# Schematic1.net
KiCad netlist of a schematic drawn in Altium Designer
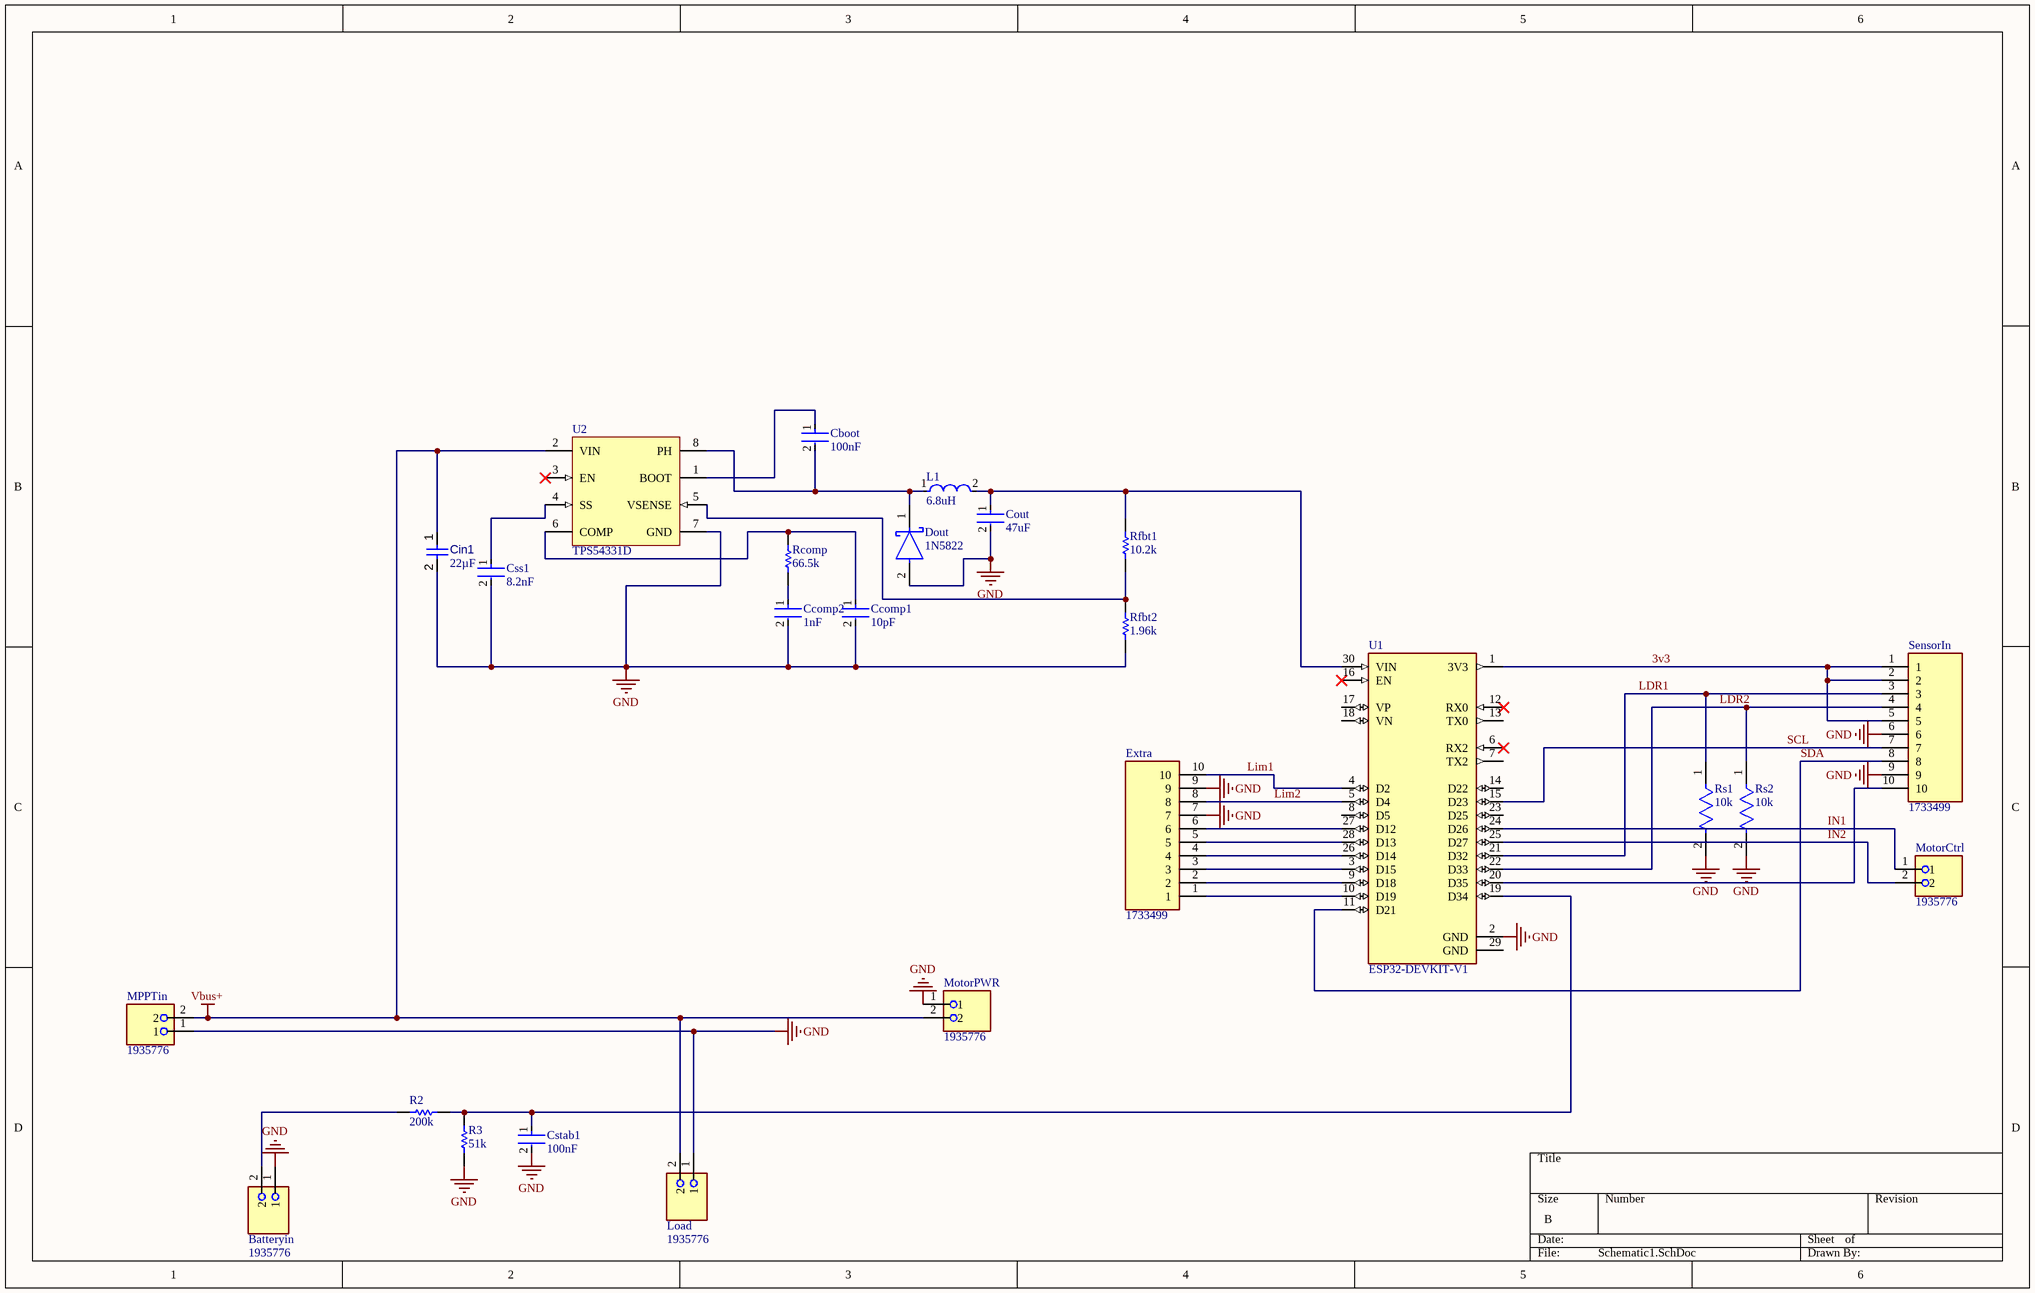
[diagram p0: Schematic1.SchDoc]

(export (version "E")
  (design (tool "Eeschema 10.0.6"))
  (components
    (comp (ref "Batteryin")
      (value "1935776")
      (footprint "PHOENIX_1935776")
      (fields (field (name "MF") "{'manufacturer': u'Phoenix Contact'}"))
      (libsource (lib "") (part "1935776_2"))
    )
    (comp (ref "Cboot")
      (value "100nF")
      (footprint "FP-CC0805-0_85-MFG")
      (description "CAP CER 0.1UF 50V X7R 0805")
      (fields (field (name "TOLERANCE") "0.1") (field (name "MANUFACTURER PART NUMBER") "CC0805KRX7R9BB104"))
      (libsource (lib "Altium Content Vault") (part "11868f565c42a9108669ba33697ecf6"))
    )
    (comp (ref "Ccomp1")
      (value "10pF")
      (footprint "FP-C0805C-DN-MFG")
      (description "Capacitor; Ceramic; Cap 10 pF; Tol 5%; Vol-Rtg 50 VDC; SMT; 0805; COG (NPO); Tape&Reel")
      (fields
        (field (name "OCTOPART") "https://octopart.com/c0805c100j5gactu-kemet-104357")
        (field (name "MANUFACTURER PART NUMBER") "C0805C100J5GACTU")
      )
      (libsource (lib "Altium Content Vault") (part "b4654b650e69147ec39a6b967a45e02"))
    )
    (comp (ref "Ccomp2")
      (value "1nF")
      (footprint "FP-CC0805-0_85-MFG")
      (description "CAP CER 0.1UF 50V X7R 0805")
      (fields (field (name "TOLERANCE") "0.1") (field (name "MANUFACTURER PART NUMBER") "CC0805KRX7R9BB104"))
      (libsource (lib "Altium Content Vault") (part "11868f565c42a9108669ba33697ecf6"))
    )
    (comp (ref "Cin1")
      (value "22µF")
      (footprint "CAPC0805(2012)145_L")
      (description "Chip Capacitor, 22µF +/-40%, 16V, 0805, Thickness 1.45 mm")
      (fields (field (name "TOLERANCE") "5%") (field (name "Comment") "Capacitor 22µF +/-40% 16V 0805"))
      (libsource (lib "Josh Mulvena") (part "CAP-NP-2"))
    )
    (comp (ref "Cout")
      (value "47uF")
      (footprint "FP-GRM21B-0_2-e0_2_0_7-IPC_A")
      (description "Chip Multilayer Ceramic Capacitors for General Purpose, 0805, 47uF, X5R, 15%, 20%, 10V")
      (fields (field (name "TOLERANCE") "20%") (field (name "VOLTAGE") "10V"))
      (libsource (lib "Altium Content Vault") (part "b4654b650e69147ec39a6b967a45e02"))
    )
    (comp (ref "Css1")
      (value "8.2nF")
      (footprint "FP-GRM219-0_1-IPC_C")
      (description "Chip Multilayer Ceramic Capacitors for General Purpose, 0805, 8200pF, C0G, 30ppm/°C, 5%, 50V")
      (fields (field (name "TOLERANCE") "5%") (field (name "VOLTAGE") "50V"))
      (libsource (lib "Altium Content Vault") (part "02cd4be3c70576c341d710602a673aa"))
    )
    (comp (ref "Cstab1")
      (value "100nF")
      (footprint "FP-CC0805-0_85-MFG")
      (description "CAP CER 0.1UF 50V X7R 0805")
      (fields (field (name "TOLERANCE") "0.1") (field (name "MANUFACTURER PART NUMBER") "CC0805KRX7R9BB104"))
      (libsource (lib "Altium Content Vault") (part "11868f565c42a9108669ba33697ecf6"))
    )
    (comp (ref "Dout")
      (value "1N5822")
      (footprint "FP-DO-201AD-MFG")
      (description "DIODE SCHOTTKY 40V 3A DO201AD")
      (fields
        (field (name "OCTOPART") "https://octopart.com/1n5822-stmicroelectronics-323225")
        (field (name "MANUFACTURER") "STMicroelectronics")
      )
      (libsource (lib "Altium Content Vault") (part "1d6ec82d83fb6aee721767c19dac4b9"))
    )
    (comp (ref "Extra")
      (value "1733499")
      (footprint "SamacSys:1733499")
      (description "Connector")
      (fields (field (name "MOUSER PART NUMBER") "651-1733499"))
      (libsource (lib "") (part "1733499_1"))
    )
    (comp (ref "L1")
      (value "6.8uH")
      (footprint "FP-MLZ2012-0_85-IPC_A")
      (description "Shielded Multilayer Inductor 6.8uH ±20% 550mA 325mΩ SMD 0805")
      (fields (field (name "TOLERANCE") "20%"))
      (libsource (lib "Altium Content Vault") (part "725321dda6339637d4d059423bc1c3c"))
    )
    (comp (ref "Load")
      (value "1935776")
      (footprint "PHOENIX_1935776")
      (fields (field (name "MF") "{'manufacturer': u'Phoenix Contact'}"))
      (libsource (lib "") (part "1935776_2"))
    )
    (comp (ref "MotorCtrl")
      (value "1935776")
      (footprint "PHOENIX_1935776")
      (fields (field (name "MF") "{'manufacturer': u'Phoenix Contact'}"))
      (libsource (lib "") (part "1935776_1"))
    )
    (comp (ref "MotorPWR")
      (value "1935776")
      (footprint "PHOENIX_1935776")
      (fields (field (name "MF") "{'manufacturer': u'Phoenix Contact'}"))
      (libsource (lib "") (part "1935776_1"))
    )
    (comp (ref "MPPTin")
      (value "1935776")
      (footprint "PHOENIX_1935776")
      (fields (field (name "MF") "{'manufacturer': u'Phoenix Contact'}"))
      (libsource (lib "1935776") (part "1935776"))
    )
    (comp (ref "R2")
      (value "200k")
      (footprint "RESC2013X50X30NL20T20")
      (fields (field (name "PART NUMBER") "CRCW0805200KJNEA") (field (name "MANUFACTURER") "Vishay Dale"))
      (libsource (lib "Altium Content Vault") (part "RES"))
    )
    (comp (ref "R3")
      (value "51k")
      (footprint "RESC2013X50X30NL20T20")
      (fields (field (name "MANUFACTURER") "Vishay Dale") (field (name "PART NUMBER") "CRCW080551K0FKEA"))
      (libsource (lib "Altium Content Vault") (part "RES"))
    )
    (comp (ref "Rcomp")
      (value "66.5k")
      (footprint "RESC2013X50X30LL20T20")
      (fields (field (name "PART NUMBER") "CRCW080566K5FKEA") (field (name "MANUFACTURER") "Vishay Dale"))
      (libsource (lib "Altium Content Vault") (part "RES"))
    )
    (comp (ref "Rfbt1")
      (value "10.2k")
      (footprint "RESC2013X50X30NL20T20")
      (fields (field (name "MANUFACTURER") "Vishay Dale") (field (name "PART NUMBER") "CRCW080510K2FKEA"))
      (libsource (lib "Altium Content Vault") (part "RES"))
    )
    (comp (ref "Rfbt2")
      (value "1.96k")
      (footprint "RESC2013X50X30LL20T20")
      (fields (field (name "PART NUMBER") "CRCW08051K96FKEA") (field (name "MANUFACTURER") "Vishay Dale"))
      (libsource (lib "Altium Content Vault") (part "RES"))
    )
    (comp (ref "Rs1")
      (value "10k")
      (footprint "FP-CRCW0805-e3-IPC_A")
      (description "RES Thick Film, 10kΩ, 1%, 0.125W, 100ppm/°C, 0805")
      (fields (field (name "TOLERANCE") "1%"))
      (libsource (lib "Altium Content Vault") (part "1029c3af85768c4190bb7ad29bc67b5"))
    )
    (comp (ref "Rs2")
      (value "10k")
      (footprint "FP-CRCW0805-e3-IPC_A")
      (description "RES Thick Film, 10kΩ, 1%, 0.125W, 100ppm/°C, 0805")
      (fields (field (name "TOLERANCE") "1%"))
      (libsource (lib "Altium Content Vault") (part "1029c3af85768c4190bb7ad29bc67b5"))
    )
    (comp (ref "SensorIn")
      (value "1733499")
      (footprint "SamacSys:1733499")
      (description "Connector")
      (fields (field (name "MOUSER PART NUMBER") "651-1733499"))
      (libsource (lib "*") (part "1733499"))
    )
    (comp (ref "U1")
      (value "ESP32-DEVKIT-V1")
      (footprint "MODULE_ESP32_DEVKIT_V1")
      (fields (field (name "MF") "Do it"))
      (libsource (lib "Josh Mulvena") (part "ESP32-DEVKIT-V1"))
    )
    (comp (ref "U2")
      (value "TPS54331D")
      (footprint "D0008A_L")
      (fields (field (name "MANUFACTURER") "Texas Instruments"))
      (libsource (lib "Altium Content Vault") (part "TI-TPS54331D8"))
    )
  )
  (nets
    (net (code "1") (name "/3v3") (class "Default")
      (node (ref "SensorIn") (pin "1") (pinfunction "1_1") (pintype "passive"))
      (node (ref "SensorIn") (pin "2") (pinfunction "2_2") (pintype "passive"))
      (node (ref "SensorIn") (pin "5") (pinfunction "5_5") (pintype "passive"))
      (node (ref "U1") (pin "1") (pinfunction "3V3_1") (pintype "output"))
    )
    (net (code "2") (name "/IN1") (class "Default")
      (node (ref "MotorCtrl") (pin "1") (pinfunction "1_1") (pintype "passive"))
      (node (ref "U1") (pin "24") (pinfunction "D26_24") (pintype "bidirectional"))
    )
    (net (code "3") (name "/IN2") (class "Default")
      (node (ref "MotorCtrl") (pin "2") (pinfunction "2_2") (pintype "passive"))
      (node (ref "U1") (pin "25") (pinfunction "D27_25") (pintype "bidirectional"))
    )
    (net (code "4") (name "/LDR1") (class "Default")
      (node (ref "Rs1") (pin "1") (pinfunction "1_1") (pintype "passive"))
      (node (ref "SensorIn") (pin "3") (pinfunction "3_3") (pintype "passive"))
      (node (ref "U1") (pin "21") (pinfunction "D32_21") (pintype "bidirectional"))
    )
    (net (code "5") (name "/LDR2") (class "Default")
      (node (ref "Rs2") (pin "1") (pinfunction "1_1") (pintype "passive"))
      (node (ref "SensorIn") (pin "4") (pinfunction "4_4") (pintype "passive"))
      (node (ref "U1") (pin "22") (pinfunction "D33_22") (pintype "bidirectional"))
    )
    (net (code "6") (name "/Lim1") (class "Default")
      (node (ref "Extra") (pin "10") (pinfunction "10_10") (pintype "passive"))
      (node (ref "U1") (pin "4") (pinfunction "D2_4") (pintype "bidirectional"))
    )
    (net (code "7") (name "/Lim2") (class "Default")
      (node (ref "Extra") (pin "8") (pinfunction "8_8") (pintype "passive"))
      (node (ref "U1") (pin "5") (pinfunction "D4_5") (pintype "bidirectional"))
    )
    (net (code "8") (name "/SCL") (class "Default")
      (node (ref "SensorIn") (pin "7") (pinfunction "7_7") (pintype "passive"))
      (node (ref "U1") (pin "15") (pinfunction "D23_15") (pintype "bidirectional"))
    )
    (net (code "9") (name "/SDA") (class "Default")
      (node (ref "SensorIn") (pin "8") (pinfunction "8_8") (pintype "passive"))
      (node (ref "U1") (pin "11") (pinfunction "D21_11") (pintype "bidirectional"))
    )
    (net (code "10") (name "GND") (class "Default")
      (node (ref "Batteryin") (pin "1") (pinfunction "1_1") (pintype "passive"))
      (node (ref "Ccomp1") (pin "2") (pinfunction "2_2") (pintype "passive"))
      (node (ref "Ccomp2") (pin "2") (pinfunction "2_2") (pintype "passive"))
      (node (ref "Cin1") (pin "2") (pinfunction "2_2") (pintype "passive"))
      (node (ref "Cout") (pin "2") (pinfunction "2_2") (pintype "passive"))
      (node (ref "Css1") (pin "2") (pinfunction "2_2") (pintype "passive"))
      (node (ref "Cstab1") (pin "2") (pinfunction "2_2") (pintype "passive"))
      (node (ref "Dout") (pin "2") (pinfunction "A_2") (pintype "passive"))
      (node (ref "Extra") (pin "7") (pinfunction "7_7") (pintype "passive"))
      (node (ref "Extra") (pin "9") (pinfunction "9_9") (pintype "passive"))
      (node (ref "Load") (pin "1") (pinfunction "1_1") (pintype "passive"))
      (node (ref "MPPTin") (pin "1") (pinfunction "1_1") (pintype "passive"))
      (node (ref "MotorPWR") (pin "1") (pinfunction "1_1") (pintype "passive"))
      (node (ref "R3") (pin "1") (pinfunction "1_1") (pintype "passive"))
      (node (ref "Rfbt2") (pin "1") (pinfunction "1_1") (pintype "passive"))
      (node (ref "Rs1") (pin "2") (pinfunction "2_2") (pintype "passive"))
      (node (ref "Rs2") (pin "2") (pinfunction "2_2") (pintype "passive"))
      (node (ref "SensorIn") (pin "6") (pinfunction "6_6") (pintype "passive"))
      (node (ref "SensorIn") (pin "9") (pinfunction "9_9") (pintype "passive"))
      (node (ref "U1") (pin "2") (pinfunction "GND_2") (pintype "power_in"))
      (node (ref "U2") (pin "7") (pinfunction "GND_7") (pintype "power_in"))
    )
    (net (code "11") (name "Net-(Batteryin-Pad2)") (class "Default")
      (node (ref "Batteryin") (pin "2") (pinfunction "2_2") (pintype "passive"))
      (node (ref "R2") (pin "1") (pinfunction "1_1") (pintype "passive"))
    )
    (net (code "12") (name "Net-(Ccomp2-Pad1)") (class "Default")
      (node (ref "Ccomp2") (pin "1") (pinfunction "1_1") (pintype "passive"))
      (node (ref "Rcomp") (pin "1") (pinfunction "1_1") (pintype "passive"))
    )
    (net (code "13") (name "Net-(Dout-C)") (class "Default")
      (node (ref "Cboot") (pin "2") (pinfunction "2_2") (pintype "passive"))
      (node (ref "Dout") (pin "1") (pinfunction "C_1") (pintype "passive"))
      (node (ref "L1") (pin "1") (pinfunction "1_1") (pintype "passive"))
      (node (ref "U2") (pin "8") (pinfunction "PH_8") (pintype "power_in"))
    )
    (net (code "14") (name "Net-(U1-D12)") (class "Default")
      (node (ref "Extra") (pin "6") (pinfunction "6_6") (pintype "passive"))
      (node (ref "U1") (pin "27") (pinfunction "D12_27") (pintype "bidirectional"))
    )
    (net (code "15") (name "Net-(U1-D13)") (class "Default")
      (node (ref "Extra") (pin "5") (pinfunction "5_5") (pintype "passive"))
      (node (ref "U1") (pin "28") (pinfunction "D13_28") (pintype "bidirectional"))
    )
    (net (code "16") (name "Net-(U1-D14)") (class "Default")
      (node (ref "Extra") (pin "4") (pinfunction "4_4") (pintype "passive"))
      (node (ref "U1") (pin "26") (pinfunction "D14_26") (pintype "bidirectional"))
    )
    (net (code "17") (name "Net-(U1-D15)") (class "Default")
      (node (ref "Extra") (pin "3") (pinfunction "3_3") (pintype "passive"))
      (node (ref "U1") (pin "3") (pinfunction "D15_3") (pintype "bidirectional"))
    )
    (net (code "18") (name "Net-(U1-D18)") (class "Default")
      (node (ref "Extra") (pin "2") (pinfunction "2_2") (pintype "passive"))
      (node (ref "U1") (pin "9") (pinfunction "D18_9") (pintype "bidirectional"))
    )
    (net (code "19") (name "Net-(U1-D19)") (class "Default")
      (node (ref "Extra") (pin "1") (pinfunction "1_1") (pintype "passive"))
      (node (ref "U1") (pin "10") (pinfunction "D19_10") (pintype "bidirectional"))
    )
    (net (code "20") (name "Net-(U1-D34)") (class "Default")
      (node (ref "Cstab1") (pin "1") (pinfunction "1_1") (pintype "passive"))
      (node (ref "R2") (pin "2") (pinfunction "2_2") (pintype "passive"))
      (node (ref "R3") (pin "2") (pinfunction "2_2") (pintype "passive"))
      (node (ref "U1") (pin "19") (pinfunction "D34_19") (pintype "bidirectional"))
    )
    (net (code "21") (name "Net-(U1-D35)") (class "Default")
      (node (ref "SensorIn") (pin "10") (pinfunction "10_10") (pintype "passive"))
      (node (ref "U1") (pin "20") (pinfunction "D35_20") (pintype "bidirectional"))
    )
    (net (code "22") (name "Net-(U1-VIN)") (class "Default")
      (node (ref "Cout") (pin "1") (pinfunction "1_1") (pintype "passive"))
      (node (ref "L1") (pin "2") (pinfunction "2_2") (pintype "passive"))
      (node (ref "Rfbt1") (pin "2") (pinfunction "2_2") (pintype "passive"))
      (node (ref "U1") (pin "30") (pinfunction "VIN_30") (pintype "input"))
    )
    (net (code "23") (name "Net-(U2-BOOT)") (class "Default")
      (node (ref "Cboot") (pin "1") (pinfunction "1_1") (pintype "passive"))
      (node (ref "U2") (pin "1") (pinfunction "BOOT_1") (pintype "passive"))
    )
    (net (code "24") (name "Net-(U2-COMP)") (class "Default")
      (node (ref "Ccomp1") (pin "1") (pinfunction "1_1") (pintype "passive"))
      (node (ref "Rcomp") (pin "2") (pinfunction "2_2") (pintype "passive"))
      (node (ref "U2") (pin "6") (pinfunction "COMP_6") (pintype "passive"))
    )
    (net (code "25") (name "Net-(U2-SS)") (class "Default")
      (node (ref "Css1") (pin "1") (pinfunction "1_1") (pintype "passive"))
      (node (ref "U2") (pin "4") (pinfunction "SS_4") (pintype "input"))
    )
    (net (code "26") (name "Net-(U2-VSENSE)") (class "Default")
      (node (ref "Rfbt1") (pin "1") (pinfunction "1_1") (pintype "passive"))
      (node (ref "Rfbt2") (pin "2") (pinfunction "2_2") (pintype "passive"))
      (node (ref "U2") (pin "5") (pinfunction "VSENSE_5") (pintype "input"))
    )
    (net (code "27") (name "Vbus+") (class "Default")
      (node (ref "Cin1") (pin "1") (pinfunction "1_1") (pintype "passive"))
      (node (ref "Load") (pin "2") (pinfunction "2_2") (pintype "passive"))
      (node (ref "MPPTin") (pin "2") (pinfunction "2_2") (pintype "passive"))
      (node (ref "MotorPWR") (pin "2") (pinfunction "2_2") (pintype "passive"))
      (node (ref "U2") (pin "2") (pinfunction "VIN_2") (pintype "power_in"))
    )
    (net (code "28") (name "unconnected-(U1-D5-Pad8)") (class "Default")
      (node (ref "U1") (pin "8") (pinfunction "D5_8") (pintype "bidirectional"))
    )
    (net (code "29") (name "unconnected-(U1-D22-Pad14)") (class "Default")
      (node (ref "U1") (pin "14") (pinfunction "D22_14") (pintype "bidirectional"))
    )
    (net (code "30") (name "unconnected-(U1-D25-Pad23)") (class "Default")
      (node (ref "U1") (pin "23") (pinfunction "D25_23") (pintype "bidirectional"))
    )
    (net (code "31") (name "unconnected-(U1-EN-Pad16)") (class "Default")
      (node (ref "U1") (pin "16") (pinfunction "EN_16") (pintype "input+no_connect"))
    )
    (net (code "32") (name "unconnected-(U1-GND-Pad29)") (class "Default")
      (node (ref "U1") (pin "29") (pinfunction "GND_29") (pintype "power_in"))
    )
    (net (code "33") (name "unconnected-(U1-RX0-Pad12)") (class "Default")
      (node (ref "U1") (pin "12") (pinfunction "RX0_12") (pintype "input+no_connect"))
    )
    (net (code "34") (name "unconnected-(U1-RX2-Pad6)") (class "Default")
      (node (ref "U1") (pin "6") (pinfunction "RX2_6") (pintype "input+no_connect"))
    )
    (net (code "35") (name "unconnected-(U1-TX0-Pad13)") (class "Default")
      (node (ref "U1") (pin "13") (pinfunction "TX0_13") (pintype "output"))
    )
    (net (code "36") (name "unconnected-(U1-TX2-Pad7)") (class "Default")
      (node (ref "U1") (pin "7") (pinfunction "TX2_7") (pintype "output"))
    )
    (net (code "37") (name "unconnected-(U1-VN-Pad18)") (class "Default")
      (node (ref "U1") (pin "18") (pinfunction "VN_18") (pintype "bidirectional"))
    )
    (net (code "38") (name "unconnected-(U1-VP-Pad17)") (class "Default")
      (node (ref "U1") (pin "17") (pinfunction "VP_17") (pintype "bidirectional"))
    )
    (net (code "39") (name "unconnected-(U2-EN-Pad3)") (class "Default")
      (node (ref "U2") (pin "3") (pinfunction "EN_3") (pintype "input+no_connect"))
    )
  )
)
